# 8iSwitchesB.net
KiCad netlist of a schematic drawn in EAGLE
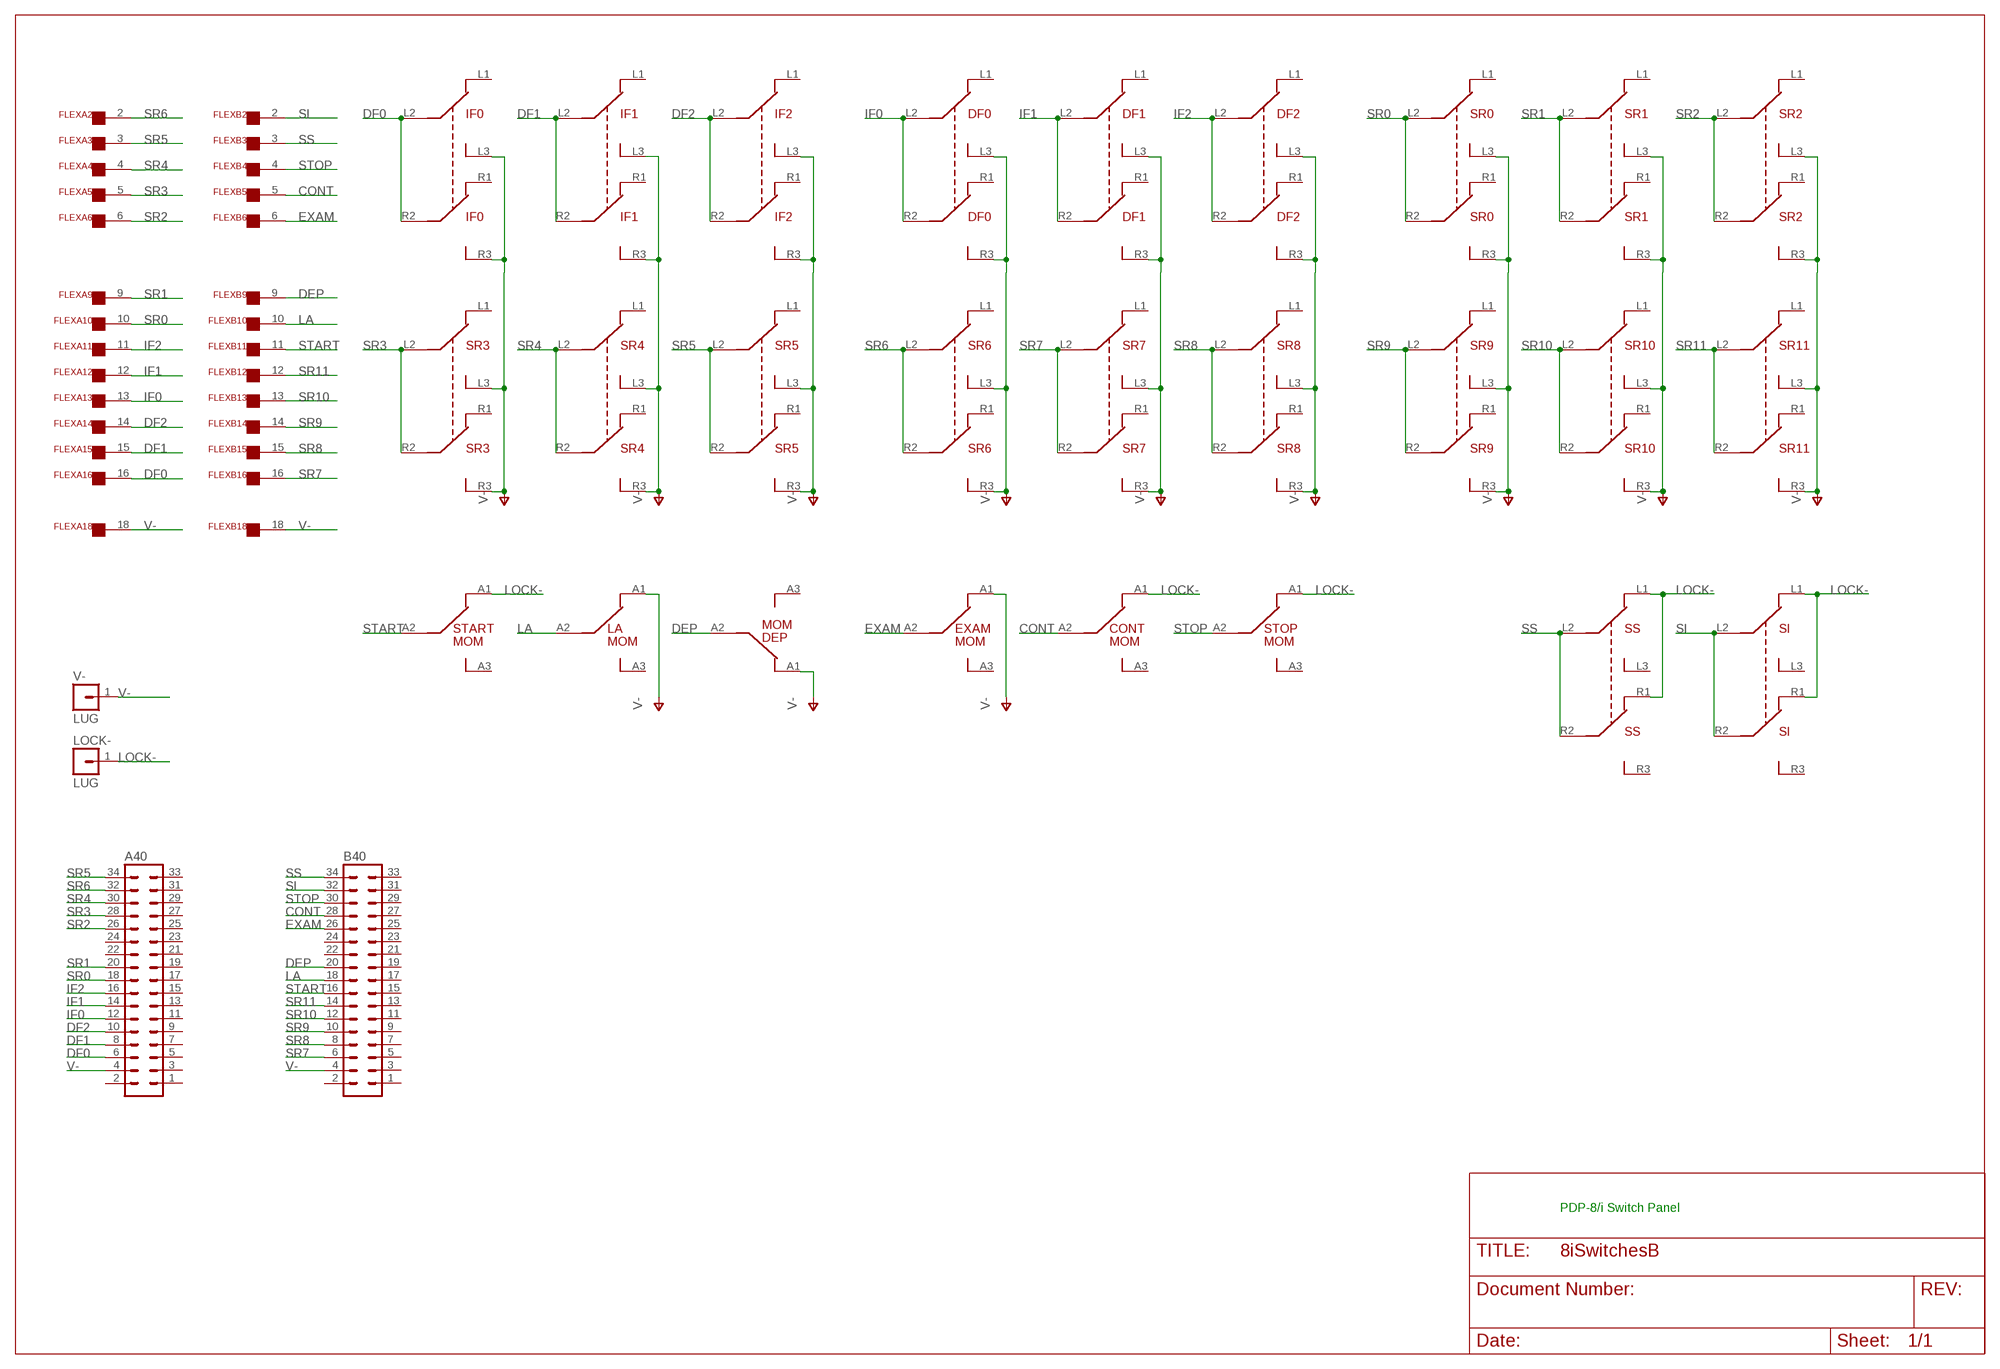
[diagram p0: schematic, sheet 1]

(export (version "E")
  (design (tool "Eeschema 10.0.6"))
  (components
    (comp (ref "A40")
      (value "MA17-2")
      (footprint "eagle-import:MA17-2")
      (libsource (lib "eagle-import") (part "MA17-2"))
    )
    (comp (ref "B40")
      (value "MA17-2")
      (footprint "eagle-import:MA17-2")
      (libsource (lib "eagle-import") (part "MA17-2"))
    )
    (comp (ref "CONT")
      (value "SPDT8I")
      (footprint "eagle-import:SPDT8I")
      (libsource (lib "eagle-import") (part "SPDT8I"))
    )
    (comp (ref "DEP")
      (value "SPDT8I")
      (footprint "eagle-import:SPDT8I")
      (libsource (lib "eagle-import") (part "SPDT8I"))
    )
    (comp (ref "DF0")
      (value "DPDT8I")
      (footprint "eagle-import:DPDT8I")
      (libsource (lib "eagle-import") (part "DPDT8I"))
    )
    (comp (ref "DF1")
      (value "DPDT8I")
      (footprint "eagle-import:DPDT8I")
      (libsource (lib "eagle-import") (part "DPDT8I"))
    )
    (comp (ref "DF2")
      (value "DPDT8I")
      (footprint "eagle-import:DPDT8I")
      (libsource (lib "eagle-import") (part "DPDT8I"))
    )
    (comp (ref "EXAM")
      (value "SPDT8I")
      (footprint "eagle-import:SPDT8I")
      (libsource (lib "eagle-import") (part "SPDT8I"))
    )
    (comp (ref "FLEXA")
      (value "FLEX19")
      (footprint "eagle-import:FLEX19")
      (libsource (lib "eagle-import") (part "FLEX19"))
    )
    (comp (ref "FLEXB")
      (value "FLEX19")
      (footprint "eagle-import:FLEX19")
      (libsource (lib "eagle-import") (part "FLEX19"))
    )
    (comp (ref "IF0")
      (value "DPDT8I")
      (footprint "eagle-import:DPDT8I")
      (libsource (lib "eagle-import") (part "DPDT8I"))
    )
    (comp (ref "IF1")
      (value "DPDT8I")
      (footprint "eagle-import:DPDT8I")
      (libsource (lib "eagle-import") (part "DPDT8I"))
    )
    (comp (ref "IF2")
      (value "DPDT8I")
      (footprint "eagle-import:DPDT8I")
      (libsource (lib "eagle-import") (part "DPDT8I"))
    )
    (comp (ref "LA")
      (value "SPDT8I")
      (footprint "eagle-import:SPDT8I")
      (libsource (lib "eagle-import") (part "SPDT8I"))
    )
    (comp (ref "LOCK-")
      (value "LUG")
      (footprint "eagle-import:SPADELUG")
      (libsource (lib "eagle-import") (part "LUG"))
    )
    (comp (ref "SI")
      (value "DPDT8I")
      (footprint "eagle-import:DPDT8I")
      (libsource (lib "eagle-import") (part "DPDT8I"))
    )
    (comp (ref "SR0")
      (value "DPDT8I")
      (footprint "eagle-import:DPDT8I")
      (libsource (lib "eagle-import") (part "DPDT8I"))
    )
    (comp (ref "SR1")
      (value "DPDT8I")
      (footprint "eagle-import:DPDT8I")
      (libsource (lib "eagle-import") (part "DPDT8I"))
    )
    (comp (ref "SR2")
      (value "DPDT8I")
      (footprint "eagle-import:DPDT8I")
      (libsource (lib "eagle-import") (part "DPDT8I"))
    )
    (comp (ref "SR3")
      (value "DPDT8I")
      (footprint "eagle-import:DPDT8I")
      (libsource (lib "eagle-import") (part "DPDT8I"))
    )
    (comp (ref "SR4")
      (value "DPDT8I")
      (footprint "eagle-import:DPDT8I")
      (libsource (lib "eagle-import") (part "DPDT8I"))
    )
    (comp (ref "SR5")
      (value "DPDT8I")
      (footprint "eagle-import:DPDT8I")
      (libsource (lib "eagle-import") (part "DPDT8I"))
    )
    (comp (ref "SR6")
      (value "DPDT8I")
      (footprint "eagle-import:DPDT8I")
      (libsource (lib "eagle-import") (part "DPDT8I"))
    )
    (comp (ref "SR7")
      (value "DPDT8I")
      (footprint "eagle-import:DPDT8I")
      (libsource (lib "eagle-import") (part "DPDT8I"))
    )
    (comp (ref "SR8")
      (value "DPDT8I")
      (footprint "eagle-import:DPDT8I")
      (libsource (lib "eagle-import") (part "DPDT8I"))
    )
    (comp (ref "SR9")
      (value "DPDT8I")
      (footprint "eagle-import:DPDT8I")
      (libsource (lib "eagle-import") (part "DPDT8I"))
    )
    (comp (ref "SR10")
      (value "DPDT8I")
      (footprint "eagle-import:DPDT8I")
      (libsource (lib "eagle-import") (part "DPDT8I"))
    )
    (comp (ref "SR11")
      (value "DPDT8I")
      (footprint "eagle-import:DPDT8I")
      (libsource (lib "eagle-import") (part "DPDT8I"))
    )
    (comp (ref "SS")
      (value "DPDT8I")
      (footprint "eagle-import:DPDT8I")
      (libsource (lib "eagle-import") (part "DPDT8I"))
    )
    (comp (ref "START")
      (value "SPDT8I")
      (footprint "eagle-import:SPDT8I")
      (libsource (lib "eagle-import") (part "SPDT8I"))
    )
    (comp (ref "STOP")
      (value "SPDT8I")
      (footprint "eagle-import:SPDT8I")
      (libsource (lib "eagle-import") (part "SPDT8I"))
    )
    (comp (ref "V-")
      (value "LUG")
      (footprint "eagle-import:SPADELUG")
      (libsource (lib "eagle-import") (part "LUG"))
    )
  )
  (nets
    (net (code "1") (name "/CONT") (class "Default")
      (node (ref "B40") (pin "28") (pinfunction "28_28") (pintype "passive"))
      (node (ref "CONT") (pin "A2") (pinfunction "A2_A2") (pintype "bidirectional"))
      (node (ref "FLEXB") (pin "5") (pinfunction "1_5") (pintype "passive"))
    )
    (net (code "2") (name "/DEP") (class "Default")
      (node (ref "B40") (pin "20") (pinfunction "20_20") (pintype "passive"))
      (node (ref "DEP") (pin "A2") (pinfunction "A2_A2") (pintype "bidirectional"))
      (node (ref "FLEXB") (pin "9") (pinfunction "1_9") (pintype "passive"))
    )
    (net (code "3") (name "/DF0") (class "Default")
      (node (ref "A40") (pin "6") (pinfunction "6_6") (pintype "passive"))
      (node (ref "FLEXA") (pin "16") (pinfunction "1_16") (pintype "passive"))
      (node (ref "IF0") (pin "L2") (pinfunction "A2_L2") (pintype "bidirectional"))
      (node (ref "IF0") (pin "R2") (pinfunction "B2_R2") (pintype "bidirectional"))
    )
    (net (code "4") (name "/DF1") (class "Default")
      (node (ref "A40") (pin "8") (pinfunction "8_8") (pintype "passive"))
      (node (ref "FLEXA") (pin "15") (pinfunction "1_15") (pintype "passive"))
      (node (ref "IF1") (pin "L2") (pinfunction "A2_L2") (pintype "bidirectional"))
      (node (ref "IF1") (pin "R2") (pinfunction "B2_R2") (pintype "bidirectional"))
    )
    (net (code "5") (name "/DF2") (class "Default")
      (node (ref "A40") (pin "10") (pinfunction "10_10") (pintype "passive"))
      (node (ref "FLEXA") (pin "14") (pinfunction "1_14") (pintype "passive"))
      (node (ref "IF2") (pin "L2") (pinfunction "A2_L2") (pintype "bidirectional"))
      (node (ref "IF2") (pin "R2") (pinfunction "B2_R2") (pintype "bidirectional"))
    )
    (net (code "6") (name "/EXAM") (class "Default")
      (node (ref "B40") (pin "26") (pinfunction "26_26") (pintype "passive"))
      (node (ref "EXAM") (pin "A2") (pinfunction "A2_A2") (pintype "bidirectional"))
      (node (ref "FLEXB") (pin "6") (pinfunction "1_6") (pintype "passive"))
    )
    (net (code "7") (name "/IF0") (class "Default")
      (node (ref "A40") (pin "12") (pinfunction "12_12") (pintype "passive"))
      (node (ref "DF0") (pin "L2") (pinfunction "A2_L2") (pintype "bidirectional"))
      (node (ref "DF0") (pin "R2") (pinfunction "B2_R2") (pintype "bidirectional"))
      (node (ref "FLEXA") (pin "13") (pinfunction "1_13") (pintype "passive"))
    )
    (net (code "8") (name "/IF1") (class "Default")
      (node (ref "A40") (pin "14") (pinfunction "14_14") (pintype "passive"))
      (node (ref "DF1") (pin "L2") (pinfunction "A2_L2") (pintype "bidirectional"))
      (node (ref "DF1") (pin "R2") (pinfunction "B2_R2") (pintype "bidirectional"))
      (node (ref "FLEXA") (pin "12") (pinfunction "1_12") (pintype "passive"))
    )
    (net (code "9") (name "/IF2") (class "Default")
      (node (ref "A40") (pin "16") (pinfunction "16_16") (pintype "passive"))
      (node (ref "DF2") (pin "L2") (pinfunction "A2_L2") (pintype "bidirectional"))
      (node (ref "DF2") (pin "R2") (pinfunction "B2_R2") (pintype "bidirectional"))
      (node (ref "FLEXA") (pin "11") (pinfunction "1_11") (pintype "passive"))
    )
    (net (code "10") (name "/LA") (class "Default")
      (node (ref "B40") (pin "18") (pinfunction "18_18") (pintype "passive"))
      (node (ref "FLEXB") (pin "10") (pinfunction "1_10") (pintype "passive"))
      (node (ref "LA") (pin "A2") (pinfunction "A2_A2") (pintype "bidirectional"))
    )
    (net (code "11") (name "/LOCK-") (class "Default")
      (node (ref "CONT") (pin "A1") (pinfunction "A1_A1") (pintype "bidirectional"))
      (node (ref "LOCK-") (pin "1") (pinfunction "1_1") (pintype "passive"))
      (node (ref "SI") (pin "L1") (pinfunction "A1_L1") (pintype "bidirectional"))
      (node (ref "SI") (pin "R1") (pinfunction "B1_R1") (pintype "bidirectional"))
      (node (ref "SS") (pin "L1") (pinfunction "A1_L1") (pintype "bidirectional"))
      (node (ref "SS") (pin "R1") (pinfunction "B1_R1") (pintype "bidirectional"))
      (node (ref "START") (pin "A1") (pinfunction "A1_A1") (pintype "bidirectional"))
      (node (ref "STOP") (pin "A1") (pinfunction "A1_A1") (pintype "bidirectional"))
    )
    (net (code "12") (name "/SI") (class "Default")
      (node (ref "B40") (pin "32") (pinfunction "32_32") (pintype "passive"))
      (node (ref "FLEXB") (pin "2") (pinfunction "1_2") (pintype "passive"))
      (node (ref "SI") (pin "L2") (pinfunction "A2_L2") (pintype "bidirectional"))
      (node (ref "SI") (pin "R2") (pinfunction "B2_R2") (pintype "bidirectional"))
    )
    (net (code "13") (name "/SR0") (class "Default")
      (node (ref "A40") (pin "18") (pinfunction "18_18") (pintype "passive"))
      (node (ref "FLEXA") (pin "10") (pinfunction "1_10") (pintype "passive"))
      (node (ref "SR0") (pin "L2") (pinfunction "A2_L2") (pintype "bidirectional"))
      (node (ref "SR0") (pin "R2") (pinfunction "B2_R2") (pintype "bidirectional"))
    )
    (net (code "14") (name "/SR1") (class "Default")
      (node (ref "A40") (pin "20") (pinfunction "20_20") (pintype "passive"))
      (node (ref "FLEXA") (pin "9") (pinfunction "1_9") (pintype "passive"))
      (node (ref "SR1") (pin "L2") (pinfunction "A2_L2") (pintype "bidirectional"))
      (node (ref "SR1") (pin "R2") (pinfunction "B2_R2") (pintype "bidirectional"))
    )
    (net (code "15") (name "/SR2") (class "Default")
      (node (ref "A40") (pin "26") (pinfunction "26_26") (pintype "passive"))
      (node (ref "FLEXA") (pin "6") (pinfunction "1_6") (pintype "passive"))
      (node (ref "SR2") (pin "L2") (pinfunction "A2_L2") (pintype "bidirectional"))
      (node (ref "SR2") (pin "R2") (pinfunction "B2_R2") (pintype "bidirectional"))
    )
    (net (code "16") (name "/SR3") (class "Default")
      (node (ref "A40") (pin "28") (pinfunction "28_28") (pintype "passive"))
      (node (ref "FLEXA") (pin "5") (pinfunction "1_5") (pintype "passive"))
      (node (ref "SR3") (pin "L2") (pinfunction "A2_L2") (pintype "bidirectional"))
      (node (ref "SR3") (pin "R2") (pinfunction "B2_R2") (pintype "bidirectional"))
    )
    (net (code "17") (name "/SR4") (class "Default")
      (node (ref "A40") (pin "30") (pinfunction "30_30") (pintype "passive"))
      (node (ref "FLEXA") (pin "4") (pinfunction "1_4") (pintype "passive"))
      (node (ref "SR4") (pin "L2") (pinfunction "A2_L2") (pintype "bidirectional"))
      (node (ref "SR4") (pin "R2") (pinfunction "B2_R2") (pintype "bidirectional"))
    )
    (net (code "18") (name "/SR5") (class "Default")
      (node (ref "A40") (pin "34") (pinfunction "34_34") (pintype "passive"))
      (node (ref "FLEXA") (pin "3") (pinfunction "1_3") (pintype "passive"))
      (node (ref "SR5") (pin "L2") (pinfunction "A2_L2") (pintype "bidirectional"))
      (node (ref "SR5") (pin "R2") (pinfunction "B2_R2") (pintype "bidirectional"))
    )
    (net (code "19") (name "/SR6") (class "Default")
      (node (ref "A40") (pin "32") (pinfunction "32_32") (pintype "passive"))
      (node (ref "FLEXA") (pin "2") (pinfunction "1_2") (pintype "passive"))
      (node (ref "SR6") (pin "L2") (pinfunction "A2_L2") (pintype "bidirectional"))
      (node (ref "SR6") (pin "R2") (pinfunction "B2_R2") (pintype "bidirectional"))
    )
    (net (code "20") (name "/SR7") (class "Default")
      (node (ref "B40") (pin "6") (pinfunction "6_6") (pintype "passive"))
      (node (ref "FLEXB") (pin "16") (pinfunction "1_16") (pintype "passive"))
      (node (ref "SR7") (pin "L2") (pinfunction "A2_L2") (pintype "bidirectional"))
      (node (ref "SR7") (pin "R2") (pinfunction "B2_R2") (pintype "bidirectional"))
    )
    (net (code "21") (name "/SR8") (class "Default")
      (node (ref "B40") (pin "8") (pinfunction "8_8") (pintype "passive"))
      (node (ref "FLEXB") (pin "15") (pinfunction "1_15") (pintype "passive"))
      (node (ref "SR8") (pin "L2") (pinfunction "A2_L2") (pintype "bidirectional"))
      (node (ref "SR8") (pin "R2") (pinfunction "B2_R2") (pintype "bidirectional"))
    )
    (net (code "22") (name "/SR9") (class "Default")
      (node (ref "B40") (pin "10") (pinfunction "10_10") (pintype "passive"))
      (node (ref "FLEXB") (pin "14") (pinfunction "1_14") (pintype "passive"))
      (node (ref "SR9") (pin "L2") (pinfunction "A2_L2") (pintype "bidirectional"))
      (node (ref "SR9") (pin "R2") (pinfunction "B2_R2") (pintype "bidirectional"))
    )
    (net (code "23") (name "/SR10") (class "Default")
      (node (ref "B40") (pin "12") (pinfunction "12_12") (pintype "passive"))
      (node (ref "FLEXB") (pin "13") (pinfunction "1_13") (pintype "passive"))
      (node (ref "SR10") (pin "L2") (pinfunction "A2_L2") (pintype "bidirectional"))
      (node (ref "SR10") (pin "R2") (pinfunction "B2_R2") (pintype "bidirectional"))
    )
    (net (code "24") (name "/SR11") (class "Default")
      (node (ref "B40") (pin "14") (pinfunction "14_14") (pintype "passive"))
      (node (ref "FLEXB") (pin "12") (pinfunction "1_12") (pintype "passive"))
      (node (ref "SR11") (pin "L2") (pinfunction "A2_L2") (pintype "bidirectional"))
      (node (ref "SR11") (pin "R2") (pinfunction "B2_R2") (pintype "bidirectional"))
    )
    (net (code "25") (name "/SS") (class "Default")
      (node (ref "B40") (pin "34") (pinfunction "34_34") (pintype "passive"))
      (node (ref "FLEXB") (pin "3") (pinfunction "1_3") (pintype "passive"))
      (node (ref "SS") (pin "L2") (pinfunction "A2_L2") (pintype "bidirectional"))
      (node (ref "SS") (pin "R2") (pinfunction "B2_R2") (pintype "bidirectional"))
    )
    (net (code "26") (name "/START") (class "Default")
      (node (ref "B40") (pin "16") (pinfunction "16_16") (pintype "passive"))
      (node (ref "FLEXB") (pin "11") (pinfunction "1_11") (pintype "passive"))
      (node (ref "START") (pin "A2") (pinfunction "A2_A2") (pintype "bidirectional"))
    )
    (net (code "27") (name "/STOP") (class "Default")
      (node (ref "B40") (pin "30") (pinfunction "30_30") (pintype "passive"))
      (node (ref "FLEXB") (pin "4") (pinfunction "1_4") (pintype "passive"))
      (node (ref "STOP") (pin "A2") (pinfunction "A2_A2") (pintype "bidirectional"))
    )
    (net (code "28") (name "V-") (class "Default")
      (node (ref "A40") (pin "4") (pinfunction "4_4") (pintype "passive"))
      (node (ref "B40") (pin "4") (pinfunction "4_4") (pintype "passive"))
      (node (ref "DEP") (pin "A1") (pinfunction "A1_A1") (pintype "bidirectional"))
      (node (ref "DF0") (pin "L3") (pinfunction "A3_L3") (pintype "bidirectional"))
      (node (ref "DF0") (pin "R3") (pinfunction "B3_R3") (pintype "bidirectional"))
      (node (ref "DF1") (pin "L3") (pinfunction "A3_L3") (pintype "bidirectional"))
      (node (ref "DF1") (pin "R3") (pinfunction "B3_R3") (pintype "bidirectional"))
      (node (ref "DF2") (pin "L3") (pinfunction "A3_L3") (pintype "bidirectional"))
      (node (ref "DF2") (pin "R3") (pinfunction "B3_R3") (pintype "bidirectional"))
      (node (ref "EXAM") (pin "A1") (pinfunction "A1_A1") (pintype "bidirectional"))
      (node (ref "FLEXA") (pin "18") (pinfunction "1_18") (pintype "passive"))
      (node (ref "FLEXB") (pin "18") (pinfunction "1_18") (pintype "passive"))
      (node (ref "IF0") (pin "L3") (pinfunction "A3_L3") (pintype "bidirectional"))
      (node (ref "IF0") (pin "R3") (pinfunction "B3_R3") (pintype "bidirectional"))
      (node (ref "IF1") (pin "L3") (pinfunction "A3_L3") (pintype "bidirectional"))
      (node (ref "IF1") (pin "R3") (pinfunction "B3_R3") (pintype "bidirectional"))
      (node (ref "IF2") (pin "L3") (pinfunction "A3_L3") (pintype "bidirectional"))
      (node (ref "IF2") (pin "R3") (pinfunction "B3_R3") (pintype "bidirectional"))
      (node (ref "LA") (pin "A1") (pinfunction "A1_A1") (pintype "bidirectional"))
      (node (ref "SR0") (pin "L3") (pinfunction "A3_L3") (pintype "bidirectional"))
      (node (ref "SR0") (pin "R3") (pinfunction "B3_R3") (pintype "bidirectional"))
      (node (ref "SR1") (pin "L3") (pinfunction "A3_L3") (pintype "bidirectional"))
      (node (ref "SR1") (pin "R3") (pinfunction "B3_R3") (pintype "bidirectional"))
      (node (ref "SR10") (pin "L3") (pinfunction "A3_L3") (pintype "bidirectional"))
      (node (ref "SR10") (pin "R3") (pinfunction "B3_R3") (pintype "bidirectional"))
      (node (ref "SR11") (pin "L3") (pinfunction "A3_L3") (pintype "bidirectional"))
      (node (ref "SR11") (pin "R3") (pinfunction "B3_R3") (pintype "bidirectional"))
      (node (ref "SR2") (pin "L3") (pinfunction "A3_L3") (pintype "bidirectional"))
      (node (ref "SR2") (pin "R3") (pinfunction "B3_R3") (pintype "bidirectional"))
      (node (ref "SR3") (pin "L3") (pinfunction "A3_L3") (pintype "bidirectional"))
      (node (ref "SR3") (pin "R3") (pinfunction "B3_R3") (pintype "bidirectional"))
      (node (ref "SR4") (pin "L3") (pinfunction "A3_L3") (pintype "bidirectional"))
      (node (ref "SR4") (pin "R3") (pinfunction "B3_R3") (pintype "bidirectional"))
      (node (ref "SR5") (pin "L3") (pinfunction "A3_L3") (pintype "bidirectional"))
      (node (ref "SR5") (pin "R3") (pinfunction "B3_R3") (pintype "bidirectional"))
      (node (ref "SR6") (pin "L3") (pinfunction "A3_L3") (pintype "bidirectional"))
      (node (ref "SR6") (pin "R3") (pinfunction "B3_R3") (pintype "bidirectional"))
      (node (ref "SR7") (pin "L3") (pinfunction "A3_L3") (pintype "bidirectional"))
      (node (ref "SR7") (pin "R3") (pinfunction "B3_R3") (pintype "bidirectional"))
      (node (ref "SR8") (pin "L3") (pinfunction "A3_L3") (pintype "bidirectional"))
      (node (ref "SR8") (pin "R3") (pinfunction "B3_R3") (pintype "bidirectional"))
      (node (ref "SR9") (pin "L3") (pinfunction "A3_L3") (pintype "bidirectional"))
      (node (ref "SR9") (pin "R3") (pinfunction "B3_R3") (pintype "bidirectional"))
      (node (ref "V-") (pin "1") (pinfunction "1_1") (pintype "passive"))
    )
    (net (code "29") (name "unconnected-(A40-Pad1)") (class "Default")
      (node (ref "A40") (pin "1") (pinfunction "1_1") (pintype "passive"))
    )
    (net (code "30") (name "unconnected-(A40-Pad2)") (class "Default")
      (node (ref "A40") (pin "2") (pinfunction "2_2") (pintype "passive"))
    )
    (net (code "31") (name "unconnected-(A40-Pad3)") (class "Default")
      (node (ref "A40") (pin "3") (pinfunction "3_3") (pintype "passive"))
    )
    (net (code "32") (name "unconnected-(A40-Pad5)") (class "Default")
      (node (ref "A40") (pin "5") (pinfunction "5_5") (pintype "passive"))
    )
    (net (code "33") (name "unconnected-(A40-Pad7)") (class "Default")
      (node (ref "A40") (pin "7") (pinfunction "7_7") (pintype "passive"))
    )
    (net (code "34") (name "unconnected-(A40-Pad9)") (class "Default")
      (node (ref "A40") (pin "9") (pinfunction "9_9") (pintype "passive"))
    )
    (net (code "35") (name "unconnected-(A40-Pad11)") (class "Default")
      (node (ref "A40") (pin "11") (pinfunction "11_11") (pintype "passive"))
    )
    (net (code "36") (name "unconnected-(A40-Pad13)") (class "Default")
      (node (ref "A40") (pin "13") (pinfunction "13_13") (pintype "passive"))
    )
    (net (code "37") (name "unconnected-(A40-Pad15)") (class "Default")
      (node (ref "A40") (pin "15") (pinfunction "15_15") (pintype "passive"))
    )
    (net (code "38") (name "unconnected-(A40-Pad17)") (class "Default")
      (node (ref "A40") (pin "17") (pinfunction "17_17") (pintype "passive"))
    )
    (net (code "39") (name "unconnected-(A40-Pad19)") (class "Default")
      (node (ref "A40") (pin "19") (pinfunction "19_19") (pintype "passive"))
    )
    (net (code "40") (name "unconnected-(A40-Pad21)") (class "Default")
      (node (ref "A40") (pin "21") (pinfunction "21_21") (pintype "passive"))
    )
    (net (code "41") (name "unconnected-(A40-Pad22)") (class "Default")
      (node (ref "A40") (pin "22") (pinfunction "22_22") (pintype "passive"))
    )
    (net (code "42") (name "unconnected-(A40-Pad23)") (class "Default")
      (node (ref "A40") (pin "23") (pinfunction "23_23") (pintype "passive"))
    )
    (net (code "43") (name "unconnected-(A40-Pad24)") (class "Default")
      (node (ref "A40") (pin "24") (pinfunction "24_24") (pintype "passive"))
    )
    (net (code "44") (name "unconnected-(A40-Pad25)") (class "Default")
      (node (ref "A40") (pin "25") (pinfunction "25_25") (pintype "passive"))
    )
    (net (code "45") (name "unconnected-(A40-Pad27)") (class "Default")
      (node (ref "A40") (pin "27") (pinfunction "27_27") (pintype "passive"))
    )
    (net (code "46") (name "unconnected-(A40-Pad29)") (class "Default")
      (node (ref "A40") (pin "29") (pinfunction "29_29") (pintype "passive"))
    )
    (net (code "47") (name "unconnected-(A40-Pad31)") (class "Default")
      (node (ref "A40") (pin "31") (pinfunction "31_31") (pintype "passive"))
    )
    (net (code "48") (name "unconnected-(A40-Pad33)") (class "Default")
      (node (ref "A40") (pin "33") (pinfunction "33_33") (pintype "passive"))
    )
    (net (code "49") (name "unconnected-(B40-Pad1)") (class "Default")
      (node (ref "B40") (pin "1") (pinfunction "1_1") (pintype "passive"))
    )
    (net (code "50") (name "unconnected-(B40-Pad2)") (class "Default")
      (node (ref "B40") (pin "2") (pinfunction "2_2") (pintype "passive"))
    )
    (net (code "51") (name "unconnected-(B40-Pad3)") (class "Default")
      (node (ref "B40") (pin "3") (pinfunction "3_3") (pintype "passive"))
    )
    (net (code "52") (name "unconnected-(B40-Pad5)") (class "Default")
      (node (ref "B40") (pin "5") (pinfunction "5_5") (pintype "passive"))
    )
    (net (code "53") (name "unconnected-(B40-Pad7)") (class "Default")
      (node (ref "B40") (pin "7") (pinfunction "7_7") (pintype "passive"))
    )
    (net (code "54") (name "unconnected-(B40-Pad9)") (class "Default")
      (node (ref "B40") (pin "9") (pinfunction "9_9") (pintype "passive"))
    )
    (net (code "55") (name "unconnected-(B40-Pad11)") (class "Default")
      (node (ref "B40") (pin "11") (pinfunction "11_11") (pintype "passive"))
    )
    (net (code "56") (name "unconnected-(B40-Pad13)") (class "Default")
      (node (ref "B40") (pin "13") (pinfunction "13_13") (pintype "passive"))
    )
    (net (code "57") (name "unconnected-(B40-Pad15)") (class "Default")
      (node (ref "B40") (pin "15") (pinfunction "15_15") (pintype "passive"))
    )
    (net (code "58") (name "unconnected-(B40-Pad17)") (class "Default")
      (node (ref "B40") (pin "17") (pinfunction "17_17") (pintype "passive"))
    )
    (net (code "59") (name "unconnected-(B40-Pad19)") (class "Default")
      (node (ref "B40") (pin "19") (pinfunction "19_19") (pintype "passive"))
    )
    (net (code "60") (name "unconnected-(B40-Pad21)") (class "Default")
      (node (ref "B40") (pin "21") (pinfunction "21_21") (pintype "passive"))
    )
    (net (code "61") (name "unconnected-(B40-Pad22)") (class "Default")
      (node (ref "B40") (pin "22") (pinfunction "22_22") (pintype "passive"))
    )
    (net (code "62") (name "unconnected-(B40-Pad23)") (class "Default")
      (node (ref "B40") (pin "23") (pinfunction "23_23") (pintype "passive"))
    )
    (net (code "63") (name "unconnected-(B40-Pad24)") (class "Default")
      (node (ref "B40") (pin "24") (pinfunction "24_24") (pintype "passive"))
    )
    (net (code "64") (name "unconnected-(B40-Pad25)") (class "Default")
      (node (ref "B40") (pin "25") (pinfunction "25_25") (pintype "passive"))
    )
    (net (code "65") (name "unconnected-(B40-Pad27)") (class "Default")
      (node (ref "B40") (pin "27") (pinfunction "27_27") (pintype "passive"))
    )
    (net (code "66") (name "unconnected-(B40-Pad29)") (class "Default")
      (node (ref "B40") (pin "29") (pinfunction "29_29") (pintype "passive"))
    )
    (net (code "67") (name "unconnected-(B40-Pad31)") (class "Default")
      (node (ref "B40") (pin "31") (pinfunction "31_31") (pintype "passive"))
    )
    (net (code "68") (name "unconnected-(B40-Pad33)") (class "Default")
      (node (ref "B40") (pin "33") (pinfunction "33_33") (pintype "passive"))
    )
    (net (code "69") (name "unconnected-(CONT-PadA3)") (class "Default")
      (node (ref "CONT") (pin "A3") (pinfunction "A3_A3") (pintype "bidirectional"))
    )
    (net (code "70") (name "unconnected-(DEP-PadA3)") (class "Default")
      (node (ref "DEP") (pin "A3") (pinfunction "A3_A3") (pintype "bidirectional"))
    )
    (net (code "71") (name "unconnected-(DF0-A1-PadL1)") (class "Default")
      (node (ref "DF0") (pin "L1") (pinfunction "A1_L1") (pintype "bidirectional"))
    )
    (net (code "72") (name "unconnected-(DF0-B1-PadR1)") (class "Default")
      (node (ref "DF0") (pin "R1") (pinfunction "B1_R1") (pintype "bidirectional"))
    )
    (net (code "73") (name "unconnected-(DF1-A1-PadL1)") (class "Default")
      (node (ref "DF1") (pin "L1") (pinfunction "A1_L1") (pintype "bidirectional"))
    )
    (net (code "74") (name "unconnected-(DF1-B1-PadR1)") (class "Default")
      (node (ref "DF1") (pin "R1") (pinfunction "B1_R1") (pintype "bidirectional"))
    )
    (net (code "75") (name "unconnected-(DF2-A1-PadL1)") (class "Default")
      (node (ref "DF2") (pin "L1") (pinfunction "A1_L1") (pintype "bidirectional"))
    )
    (net (code "76") (name "unconnected-(DF2-B1-PadR1)") (class "Default")
      (node (ref "DF2") (pin "R1") (pinfunction "B1_R1") (pintype "bidirectional"))
    )
    (net (code "77") (name "unconnected-(EXAM-PadA3)") (class "Default")
      (node (ref "EXAM") (pin "A3") (pinfunction "A3_A3") (pintype "bidirectional"))
    )
    (net (code "78") (name "unconnected-(IF0-A1-PadL1)") (class "Default")
      (node (ref "IF0") (pin "L1") (pinfunction "A1_L1") (pintype "bidirectional"))
    )
    (net (code "79") (name "unconnected-(IF0-B1-PadR1)") (class "Default")
      (node (ref "IF0") (pin "R1") (pinfunction "B1_R1") (pintype "bidirectional"))
    )
    (net (code "80") (name "unconnected-(IF1-A1-PadL1)") (class "Default")
      (node (ref "IF1") (pin "L1") (pinfunction "A1_L1") (pintype "bidirectional"))
    )
    (net (code "81") (name "unconnected-(IF1-B1-PadR1)") (class "Default")
      (node (ref "IF1") (pin "R1") (pinfunction "B1_R1") (pintype "bidirectional"))
    )
    (net (code "82") (name "unconnected-(IF2-A1-PadL1)") (class "Default")
      (node (ref "IF2") (pin "L1") (pinfunction "A1_L1") (pintype "bidirectional"))
    )
    (net (code "83") (name "unconnected-(IF2-B1-PadR1)") (class "Default")
      (node (ref "IF2") (pin "R1") (pinfunction "B1_R1") (pintype "bidirectional"))
    )
    (net (code "84") (name "unconnected-(LA-PadA3)") (class "Default")
      (node (ref "LA") (pin "A3") (pinfunction "A3_A3") (pintype "bidirectional"))
    )
    (net (code "85") (name "unconnected-(SI-A3-PadL3)") (class "Default")
      (node (ref "SI") (pin "L3") (pinfunction "A3_L3") (pintype "bidirectional"))
    )
    (net (code "86") (name "unconnected-(SI-B3-PadR3)") (class "Default")
      (node (ref "SI") (pin "R3") (pinfunction "B3_R3") (pintype "bidirectional"))
    )
    (net (code "87") (name "unconnected-(SR0-A1-PadL1)") (class "Default")
      (node (ref "SR0") (pin "L1") (pinfunction "A1_L1") (pintype "bidirectional"))
    )
    (net (code "88") (name "unconnected-(SR0-B1-PadR1)") (class "Default")
      (node (ref "SR0") (pin "R1") (pinfunction "B1_R1") (pintype "bidirectional"))
    )
    (net (code "89") (name "unconnected-(SR1-A1-PadL1)") (class "Default")
      (node (ref "SR1") (pin "L1") (pinfunction "A1_L1") (pintype "bidirectional"))
    )
    (net (code "90") (name "unconnected-(SR1-B1-PadR1)") (class "Default")
      (node (ref "SR1") (pin "R1") (pinfunction "B1_R1") (pintype "bidirectional"))
    )
    (net (code "91") (name "unconnected-(SR2-A1-PadL1)") (class "Default")
      (node (ref "SR2") (pin "L1") (pinfunction "A1_L1") (pintype "bidirectional"))
    )
    (net (code "92") (name "unconnected-(SR2-B1-PadR1)") (class "Default")
      (node (ref "SR2") (pin "R1") (pinfunction "B1_R1") (pintype "bidirectional"))
    )
    (net (code "93") (name "unconnected-(SR3-A1-PadL1)") (class "Default")
      (node (ref "SR3") (pin "L1") (pinfunction "A1_L1") (pintype "bidirectional"))
    )
    (net (code "94") (name "unconnected-(SR3-B1-PadR1)") (class "Default")
      (node (ref "SR3") (pin "R1") (pinfunction "B1_R1") (pintype "bidirectional"))
    )
    (net (code "95") (name "unconnected-(SR4-A1-PadL1)") (class "Default")
      (node (ref "SR4") (pin "L1") (pinfunction "A1_L1") (pintype "bidirectional"))
    )
    (net (code "96") (name "unconnected-(SR4-B1-PadR1)") (class "Default")
      (node (ref "SR4") (pin "R1") (pinfunction "B1_R1") (pintype "bidirectional"))
    )
    (net (code "97") (name "unconnected-(SR5-A1-PadL1)") (class "Default")
      (node (ref "SR5") (pin "L1") (pinfunction "A1_L1") (pintype "bidirectional"))
    )
    (net (code "98") (name "unconnected-(SR5-B1-PadR1)") (class "Default")
      (node (ref "SR5") (pin "R1") (pinfunction "B1_R1") (pintype "bidirectional"))
    )
    (net (code "99") (name "unconnected-(SR6-A1-PadL1)") (class "Default")
      (node (ref "SR6") (pin "L1") (pinfunction "A1_L1") (pintype "bidirectional"))
    )
    (net (code "100") (name "unconnected-(SR6-B1-PadR1)") (class "Default")
      (node (ref "SR6") (pin "R1") (pinfunction "B1_R1") (pintype "bidirectional"))
    )
    (net (code "101") (name "unconnected-(SR7-A1-PadL1)") (class "Default")
      (node (ref "SR7") (pin "L1") (pinfunction "A1_L1") (pintype "bidirectional"))
    )
    (net (code "102") (name "unconnected-(SR7-B1-PadR1)") (class "Default")
      (node (ref "SR7") (pin "R1") (pinfunction "B1_R1") (pintype "bidirectional"))
    )
    (net (code "103") (name "unconnected-(SR8-A1-PadL1)") (class "Default")
      (node (ref "SR8") (pin "L1") (pinfunction "A1_L1") (pintype "bidirectional"))
    )
    (net (code "104") (name "unconnected-(SR8-B1-PadR1)") (class "Default")
      (node (ref "SR8") (pin "R1") (pinfunction "B1_R1") (pintype "bidirectional"))
    )
    (net (code "105") (name "unconnected-(SR9-A1-PadL1)") (class "Default")
      (node (ref "SR9") (pin "L1") (pinfunction "A1_L1") (pintype "bidirectional"))
    )
    (net (code "106") (name "unconnected-(SR9-B1-PadR1)") (class "Default")
      (node (ref "SR9") (pin "R1") (pinfunction "B1_R1") (pintype "bidirectional"))
    )
    (net (code "107") (name "unconnected-(SR10-A1-PadL1)") (class "Default")
      (node (ref "SR10") (pin "L1") (pinfunction "A1_L1") (pintype "bidirectional"))
    )
    (net (code "108") (name "unconnected-(SR10-B1-PadR1)") (class "Default")
      (node (ref "SR10") (pin "R1") (pinfunction "B1_R1") (pintype "bidirectional"))
    )
    (net (code "109") (name "unconnected-(SR11-A1-PadL1)") (class "Default")
      (node (ref "SR11") (pin "L1") (pinfunction "A1_L1") (pintype "bidirectional"))
    )
    (net (code "110") (name "unconnected-(SR11-B1-PadR1)") (class "Default")
      (node (ref "SR11") (pin "R1") (pinfunction "B1_R1") (pintype "bidirectional"))
    )
    (net (code "111") (name "unconnected-(SS-A3-PadL3)") (class "Default")
      (node (ref "SS") (pin "L3") (pinfunction "A3_L3") (pintype "bidirectional"))
    )
    (net (code "112") (name "unconnected-(SS-B3-PadR3)") (class "Default")
      (node (ref "SS") (pin "R3") (pinfunction "B3_R3") (pintype "bidirectional"))
    )
    (net (code "113") (name "unconnected-(START-PadA3)") (class "Default")
      (node (ref "START") (pin "A3") (pinfunction "A3_A3") (pintype "bidirectional"))
    )
    (net (code "114") (name "unconnected-(STOP-PadA3)") (class "Default")
      (node (ref "STOP") (pin "A3") (pinfunction "A3_A3") (pintype "bidirectional"))
    )
  )
)
